# schematic.net
KiCad netlist of a schematic drawn in EAGLE
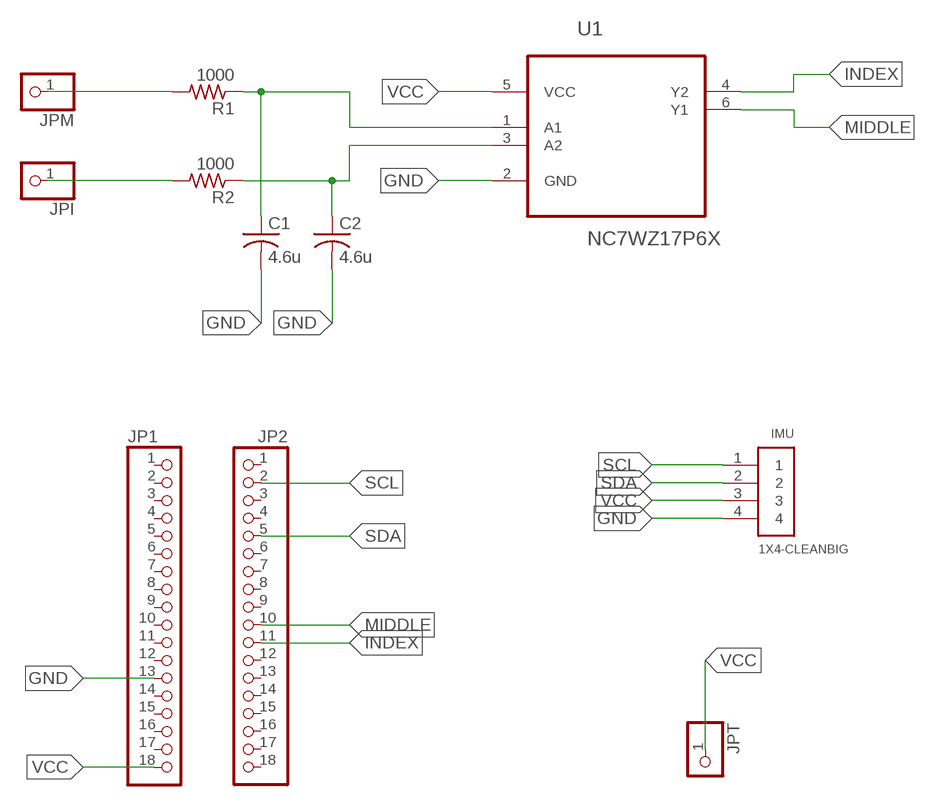
[diagram p0: schematic, sheet 1]

(export (version "E")
  (design (tool "Eeschema 10.0.6"))
  (components
    (comp (ref "C1")
      (value "4.6u")
      (footprint "eagle-import:C0805")
      (libsource (lib "eagle-import") (part "C-USC0805"))
    )
    (comp (ref "C2")
      (value "4.6u")
      (footprint "eagle-import:C0805")
      (libsource (lib "eagle-import") (part "C-USC0805"))
    )
    (comp (ref "IMU")
      (value "1X4-CLEANBIG")
      (footprint "eagle-import:1X04-CLEANBIG")
      (libsource (lib "eagle-import") (part "1X4-CLEANBIG"))
    )
    (comp (ref "JP1")
      (value "PINHD-1X18-BIG")
      (footprint "eagle-import:1X18-BIG")
      (libsource (lib "eagle-import") (part "PINHD-1X18-BIG"))
    )
    (comp (ref "JP2")
      (value "PINHD-1X18-BIG")
      (footprint "eagle-import:1X18-BIG")
      (libsource (lib "eagle-import") (part "PINHD-1X18-BIG"))
    )
    (comp (ref "JPI")
      (value "PINHD-1X1CB")
      (footprint "eagle-import:1X01-CLEANBIG")
      (libsource (lib "eagle-import") (part "PINHD-1X1CB"))
    )
    (comp (ref "JPM")
      (value "PINHD-1X1CB")
      (footprint "eagle-import:1X01-CLEANBIG")
      (libsource (lib "eagle-import") (part "PINHD-1X1CB"))
    )
    (comp (ref "JPT")
      (value "PINHD-1X1CB")
      (footprint "eagle-import:1X01-CLEANBIG")
      (libsource (lib "eagle-import") (part "PINHD-1X1CB"))
    )
    (comp (ref "R1")
      (value "1000")
      (footprint "eagle-import:M0805")
      (libsource (lib "eagle-import") (part "R-US_M0805"))
    )
    (comp (ref "R2")
      (value "1000")
      (footprint "eagle-import:M0805")
      (libsource (lib "eagle-import") (part "R-US_M0805"))
    )
    (comp (ref "U1")
      (value "NC7WZ17P6X")
      (footprint "eagle-import:SOT65P210X110-6N")
      (fields (field (name "DIGI-KEY_PART_NUMBER") "NC7WZ17P6XCT-ND") (field (name "MF") "ON Semiconductor"))
      (libsource (lib "eagle-import") (part "NC7WZ17P6X"))
    )
  )
  (nets
    (net (code "1") (name "GND") (class "Default")
      (node (ref "C1") (pin "2") (pinfunction "2_2") (pintype "passive"))
      (node (ref "C2") (pin "2") (pinfunction "2_2") (pintype "passive"))
      (node (ref "IMU") (pin "4") (pinfunction "4_4") (pintype "bidirectional"))
      (node (ref "JP1") (pin "13") (pinfunction "13_13") (pintype "passive"))
      (node (ref "U1") (pin "2") (pinfunction "GND_2") (pintype "passive"))
    )
    (net (code "2") (name "INDEX") (class "Default")
      (node (ref "JP2") (pin "11") (pinfunction "11_11") (pintype "passive"))
      (node (ref "U1") (pin "4") (pinfunction "Y2_4") (pintype "output"))
    )
    (net (code "3") (name "MIDDLE") (class "Default")
      (node (ref "JP2") (pin "10") (pinfunction "10_10") (pintype "passive"))
      (node (ref "U1") (pin "6") (pinfunction "Y1_6") (pintype "output"))
    )
    (net (code "4") (name "Net-(JPI-Pad1)") (class "Default")
      (node (ref "JPI") (pin "1") (pinfunction "1_1") (pintype "passive"))
      (node (ref "R2") (pin "2") (pinfunction "2_2") (pintype "passive"))
    )
    (net (code "5") (name "Net-(JPM-Pad1)") (class "Default")
      (node (ref "JPM") (pin "1") (pinfunction "1_1") (pintype "passive"))
      (node (ref "R1") (pin "2") (pinfunction "2_2") (pintype "passive"))
    )
    (net (code "6") (name "Net-(U1-A1)") (class "Default")
      (node (ref "C1") (pin "1") (pinfunction "1_1") (pintype "passive"))
      (node (ref "R1") (pin "1") (pinfunction "1_1") (pintype "passive"))
      (node (ref "U1") (pin "1") (pinfunction "A1_1") (pintype "input"))
    )
    (net (code "7") (name "Net-(U1-A2)") (class "Default")
      (node (ref "C2") (pin "1") (pinfunction "1_1") (pintype "passive"))
      (node (ref "R2") (pin "1") (pinfunction "1_1") (pintype "passive"))
      (node (ref "U1") (pin "3") (pinfunction "A2_3") (pintype "input"))
    )
    (net (code "8") (name "SCL") (class "Default")
      (node (ref "IMU") (pin "1") (pinfunction "1_1") (pintype "bidirectional"))
      (node (ref "JP2") (pin "2") (pinfunction "2_2") (pintype "passive"))
    )
    (net (code "9") (name "SDA") (class "Default")
      (node (ref "IMU") (pin "2") (pinfunction "2_2") (pintype "bidirectional"))
      (node (ref "JP2") (pin "5") (pinfunction "5_5") (pintype "passive"))
    )
    (net (code "10") (name "VCC") (class "Default")
      (node (ref "IMU") (pin "3") (pinfunction "3_3") (pintype "bidirectional"))
      (node (ref "JP1") (pin "18") (pinfunction "18_18") (pintype "passive"))
      (node (ref "JPT") (pin "1") (pinfunction "1_1") (pintype "passive"))
      (node (ref "U1") (pin "5") (pinfunction "VCC_5") (pintype "power_in"))
    )
    (net (code "11") (name "unconnected-(JP1-Pad1)") (class "Default")
      (node (ref "JP1") (pin "1") (pinfunction "1_1") (pintype "passive"))
    )
    (net (code "12") (name "unconnected-(JP1-Pad2)") (class "Default")
      (node (ref "JP1") (pin "2") (pinfunction "2_2") (pintype "passive"))
    )
    (net (code "13") (name "unconnected-(JP1-Pad3)") (class "Default")
      (node (ref "JP1") (pin "3") (pinfunction "3_3") (pintype "passive"))
    )
    (net (code "14") (name "unconnected-(JP1-Pad4)") (class "Default")
      (node (ref "JP1") (pin "4") (pinfunction "4_4") (pintype "passive"))
    )
    (net (code "15") (name "unconnected-(JP1-Pad5)") (class "Default")
      (node (ref "JP1") (pin "5") (pinfunction "5_5") (pintype "passive"))
    )
    (net (code "16") (name "unconnected-(JP1-Pad6)") (class "Default")
      (node (ref "JP1") (pin "6") (pinfunction "6_6") (pintype "passive"))
    )
    (net (code "17") (name "unconnected-(JP1-Pad7)") (class "Default")
      (node (ref "JP1") (pin "7") (pinfunction "7_7") (pintype "passive"))
    )
    (net (code "18") (name "unconnected-(JP1-Pad8)") (class "Default")
      (node (ref "JP1") (pin "8") (pinfunction "8_8") (pintype "passive"))
    )
    (net (code "19") (name "unconnected-(JP1-Pad9)") (class "Default")
      (node (ref "JP1") (pin "9") (pinfunction "9_9") (pintype "passive"))
    )
    (net (code "20") (name "unconnected-(JP1-Pad10)") (class "Default")
      (node (ref "JP1") (pin "10") (pinfunction "10_10") (pintype "passive"))
    )
    (net (code "21") (name "unconnected-(JP1-Pad11)") (class "Default")
      (node (ref "JP1") (pin "11") (pinfunction "11_11") (pintype "passive"))
    )
    (net (code "22") (name "unconnected-(JP1-Pad12)") (class "Default")
      (node (ref "JP1") (pin "12") (pinfunction "12_12") (pintype "passive"))
    )
    (net (code "23") (name "unconnected-(JP1-Pad14)") (class "Default")
      (node (ref "JP1") (pin "14") (pinfunction "14_14") (pintype "passive"))
    )
    (net (code "24") (name "unconnected-(JP1-Pad15)") (class "Default")
      (node (ref "JP1") (pin "15") (pinfunction "15_15") (pintype "passive"))
    )
    (net (code "25") (name "unconnected-(JP1-Pad16)") (class "Default")
      (node (ref "JP1") (pin "16") (pinfunction "16_16") (pintype "passive"))
    )
    (net (code "26") (name "unconnected-(JP1-Pad17)") (class "Default")
      (node (ref "JP1") (pin "17") (pinfunction "17_17") (pintype "passive"))
    )
    (net (code "27") (name "unconnected-(JP2-Pad1)") (class "Default")
      (node (ref "JP2") (pin "1") (pinfunction "1_1") (pintype "passive"))
    )
    (net (code "28") (name "unconnected-(JP2-Pad3)") (class "Default")
      (node (ref "JP2") (pin "3") (pinfunction "3_3") (pintype "passive"))
    )
    (net (code "29") (name "unconnected-(JP2-Pad4)") (class "Default")
      (node (ref "JP2") (pin "4") (pinfunction "4_4") (pintype "passive"))
    )
    (net (code "30") (name "unconnected-(JP2-Pad6)") (class "Default")
      (node (ref "JP2") (pin "6") (pinfunction "6_6") (pintype "passive"))
    )
    (net (code "31") (name "unconnected-(JP2-Pad7)") (class "Default")
      (node (ref "JP2") (pin "7") (pinfunction "7_7") (pintype "passive"))
    )
    (net (code "32") (name "unconnected-(JP2-Pad8)") (class "Default")
      (node (ref "JP2") (pin "8") (pinfunction "8_8") (pintype "passive"))
    )
    (net (code "33") (name "unconnected-(JP2-Pad9)") (class "Default")
      (node (ref "JP2") (pin "9") (pinfunction "9_9") (pintype "passive"))
    )
    (net (code "34") (name "unconnected-(JP2-Pad12)") (class "Default")
      (node (ref "JP2") (pin "12") (pinfunction "12_12") (pintype "passive"))
    )
    (net (code "35") (name "unconnected-(JP2-Pad13)") (class "Default")
      (node (ref "JP2") (pin "13") (pinfunction "13_13") (pintype "passive"))
    )
    (net (code "36") (name "unconnected-(JP2-Pad14)") (class "Default")
      (node (ref "JP2") (pin "14") (pinfunction "14_14") (pintype "passive"))
    )
    (net (code "37") (name "unconnected-(JP2-Pad15)") (class "Default")
      (node (ref "JP2") (pin "15") (pinfunction "15_15") (pintype "passive"))
    )
    (net (code "38") (name "unconnected-(JP2-Pad16)") (class "Default")
      (node (ref "JP2") (pin "16") (pinfunction "16_16") (pintype "passive"))
    )
    (net (code "39") (name "unconnected-(JP2-Pad17)") (class "Default")
      (node (ref "JP2") (pin "17") (pinfunction "17_17") (pintype "passive"))
    )
    (net (code "40") (name "unconnected-(JP2-Pad18)") (class "Default")
      (node (ref "JP2") (pin "18") (pinfunction "18_18") (pintype "passive"))
    )
  )
)
